# Un_51_V1_0.net
KiCad netlist of a schematic drawn in EAGLE
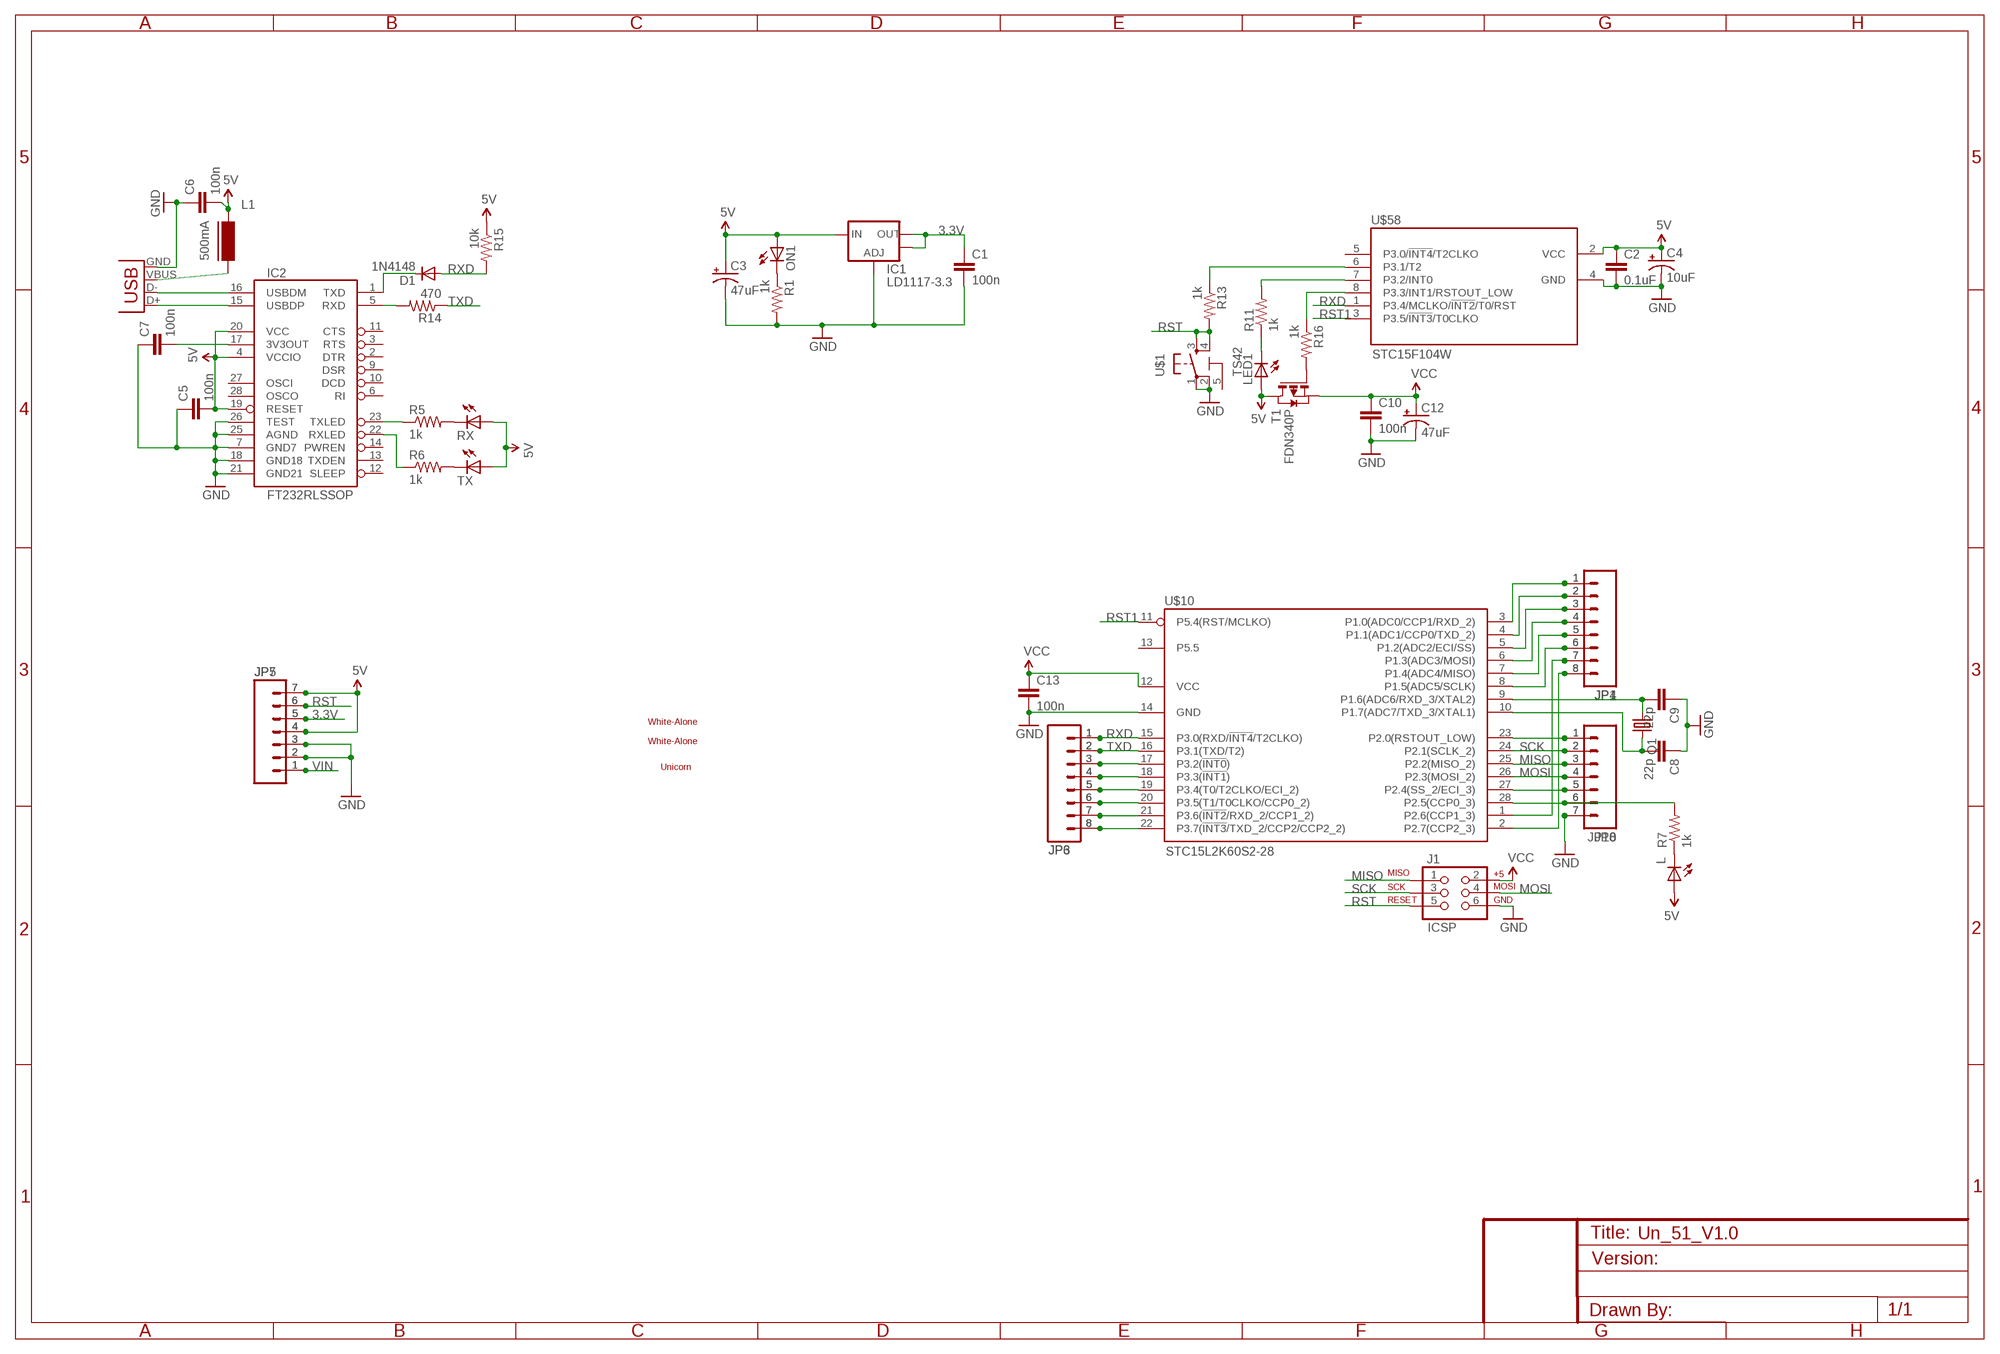
[diagram p0: schematic, sheet 1]

(export (version "E")
  (design (tool "Eeschema 10.0.6"))
  (components
    (comp (ref "C1")
      (value "100n")
      (footprint "eagle-import:0603-CAP")
      (libsource (lib "eagle-import") (part "2SparkFun_CAP0603-CAP"))
    )
    (comp (ref "C2")
      (value "0.1uF")
      (footprint "eagle-import:0603-CAP")
      (libsource (lib "eagle-import") (part "2SparkFun_CAP0603-CAP"))
    )
    (comp (ref "C3")
      (value "47uF")
      (footprint "eagle-import:PANASONIC_D")
      (libsource (lib "eagle-import") (part "CAP_POLD"))
    )
    (comp (ref "C4")
      (value "10uF")
      (footprint "eagle-import:EIA3216")
      (libsource (lib "eagle-import") (part "CAP_POL1206"))
    )
    (comp (ref "C5")
      (value "100n")
      (footprint "eagle-import:0603-CAP")
      (libsource (lib "eagle-import") (part "2SparkFun_CAP0603-CAP"))
    )
    (comp (ref "C6")
      (value "100n")
      (footprint "eagle-import:0603-CAP")
      (libsource (lib "eagle-import") (part "2SparkFun_CAP0603-CAP"))
    )
    (comp (ref "C7")
      (value "100n")
      (footprint "eagle-import:0603-CAP")
      (libsource (lib "eagle-import") (part "2SparkFun_CAP0603-CAP"))
    )
    (comp (ref "C8")
      (value "22p")
      (footprint "eagle-import:0603-CAP")
      (libsource (lib "eagle-import") (part "2SparkFun_CAP0603-CAP"))
    )
    (comp (ref "C9")
      (value "22p")
      (footprint "eagle-import:0603-CAP")
      (libsource (lib "eagle-import") (part "2SparkFun_CAP0603-CAP"))
    )
    (comp (ref "C10")
      (value "100n")
      (footprint "eagle-import:0603-CAP")
      (libsource (lib "eagle-import") (part "2SparkFun_CAP0603-CAP"))
    )
    (comp (ref "C12")
      (value "47uF")
      (footprint "eagle-import:PANASONIC_D")
      (libsource (lib "eagle-import") (part "CAP_POLD"))
    )
    (comp (ref "C13")
      (value "100n")
      (footprint "eagle-import:0603-CAP")
      (libsource (lib "eagle-import") (part "CAP0603-CAP"))
    )
    (comp (ref "D1")
      (value "1N4148")
      (footprint "eagle-import:SOD-323")
      (libsource (lib "eagle-import") (part "DIODESOD"))
    )
    (comp (ref "IC1")
      (value "LD1117-3.3")
      (footprint "eagle-import:SOT223")
      (libsource (lib "eagle-import") (part "V_REG_LM1117SOT223"))
    )
    (comp (ref "IC2")
      (value "FT232RLSSOP")
      (footprint "eagle-import:SSOP28DB")
      (libsource (lib "eagle-import") (part "FT232RLSSOP"))
    )
    (comp (ref "J1")
      (value "ICSP")
      (footprint "eagle-import:2X3")
      (libsource (lib "eagle-import") (part "AVR_SPI_PRG_6PTH"))
    )
    (comp (ref "JP1")
      (value "M081X08")
      (footprint "eagle-import:1X08")
      (libsource (lib "eagle-import") (part "M081X08"))
    )
    (comp (ref "JP3")
      (value "M08")
      (footprint "eagle-import:1X08")
      (libsource (lib "eagle-import") (part "M08"))
    )
    (comp (ref "JP4")
      (value "M081X08")
      (footprint "eagle-import:1X08")
      (libsource (lib "eagle-import") (part "M081X08"))
    )
    (comp (ref "JP5")
      (value "M07")
      (footprint "eagle-import:1X07")
      (libsource (lib "eagle-import") (part "M07"))
    )
    (comp (ref "JP6")
      (value "M08")
      (footprint "eagle-import:1X08")
      (libsource (lib "eagle-import") (part "M08"))
    )
    (comp (ref "JP7")
      (value "M07")
      (footprint "eagle-import:1X07")
      (libsource (lib "eagle-import") (part "M07"))
    )
    (comp (ref "JP8")
      (value "M07")
      (footprint "eagle-import:1X07")
      (libsource (lib "eagle-import") (part "M07"))
    )
    (comp (ref "JP10")
      (value "M07")
      (footprint "eagle-import:1X07")
      (libsource (lib "eagle-import") (part "M07"))
    )
    (comp (ref "L")
      (value "LED0805")
      (footprint "eagle-import:LED-0805")
      (libsource (lib "eagle-import") (part "LED0805"))
    )
    (comp (ref "L1")
      (value "500mA")
      (footprint "eagle-import:FB805")
      (libsource (lib "eagle-import") (part "FERRITE-0805"))
    )
    (comp (ref "LED1")
      (value "LED0805")
      (footprint "eagle-import:LED-0805")
      (libsource (lib "eagle-import") (part "2SparkFun_LED0805"))
    )
    (comp (ref "ON1")
      (value "LED0805")
      (footprint "eagle-import:LED-0805")
      (libsource (lib "eagle-import") (part "LED0805"))
    )
    (comp (ref "Q1")
      (value "CRYSTALHC49US")
      (footprint "eagle-import:HC49US")
      (libsource (lib "eagle-import") (part "CRYSTALHC49US"))
    )
    (comp (ref "R1")
      (value "1k")
      (footprint "eagle-import:0603-RES")
      (libsource (lib "eagle-import") (part "RESISTOR0603-RES"))
    )
    (comp (ref "R5")
      (value "1k")
      (footprint "eagle-import:0603-RES")
      (libsource (lib "eagle-import") (part "RESISTOR0603-RES"))
    )
    (comp (ref "R6")
      (value "1k")
      (footprint "eagle-import:0603-RES")
      (libsource (lib "eagle-import") (part "RESISTOR0603-RES"))
    )
    (comp (ref "R7")
      (value "1k")
      (footprint "eagle-import:0603-RES")
      (libsource (lib "eagle-import") (part "RESISTOR0603-RES"))
    )
    (comp (ref "R11")
      (value "1k")
      (footprint "eagle-import:0603-RES")
      (libsource (lib "eagle-import") (part "RESISTOR0603-RES"))
    )
    (comp (ref "R13")
      (value "1k")
      (footprint "eagle-import:0603-RES")
      (libsource (lib "eagle-import") (part "RESISTOR0603-RES"))
    )
    (comp (ref "R14")
      (value "470")
      (footprint "eagle-import:0603-RES")
      (libsource (lib "eagle-import") (part "RESISTOR0603-RES"))
    )
    (comp (ref "R15")
      (value "10k")
      (footprint "eagle-import:0603-RES")
      (libsource (lib "eagle-import") (part "RESISTOR0603-RES"))
    )
    (comp (ref "R16")
      (value "1k")
      (footprint "eagle-import:0603-RES")
      (libsource (lib "eagle-import") (part "RESISTOR0603-RES"))
    )
    (comp (ref "RX")
      (value "LED0805")
      (footprint "eagle-import:LED-0805")
      (libsource (lib "eagle-import") (part "LED0805"))
    )
    (comp (ref "T1")
      (value "FDN340P")
      (footprint "eagle-import:SOT-23")
      (libsource (lib "eagle-import") (part "PMOSSOT23"))
    )
    (comp (ref "TX")
      (value "LED0805")
      (footprint "eagle-import:LED-0805")
      (libsource (lib "eagle-import") (part "LED0805"))
    )
    (comp (ref "U$1")
      (value "TS42")
      (footprint "eagle-import:TS42")
      (libsource (lib "eagle-import") (part "TS42"))
    )
    (comp (ref "U$3")
      (value "UNICORN")
      (footprint "eagle-import:UNICORN_1")
      (libsource (lib "eagle-import") (part "UNICORN"))
    )
    (comp (ref "U$7")
      (value "WHITE-ALONE_0")
      (footprint "eagle-import:WHITE-ALONE_0")
      (libsource (lib "eagle-import") (part "WHITE-ALONE_0"))
    )
    (comp (ref "U$10")
      (value "STC15L2K60S2-28")
      (footprint "eagle-import:SO-28W")
      (libsource (lib "eagle-import") (part "STC15L2K60S2-28"))
    )
    (comp (ref "U$11")
      (value "WHITE-ALONE_0")
      (footprint "eagle-import:WHITE-ALONE_0")
      (libsource (lib "eagle-import") (part "WHITE-ALONE_0"))
    )
    (comp (ref "U$58")
      (value "STC15F104W")
      (footprint "eagle-import:SO08")
      (libsource (lib "eagle-import") (part "STC15F104W"))
    )
    (comp (ref "X1")
      (value "USBSMD")
      (footprint "eagle-import:USB-MINIB")
      (libsource (lib "eagle-import") (part "USBSMD"))
    )
  )
  (nets
    (net (code "1") (name "/3.3V") (class "Default")
      (node (ref "C1") (pin "1") (pinfunction "1_1") (pintype "passive"))
      (node (ref "IC1") (pin "2") (pinfunction "OUT_2") (pintype "output"))
      (node (ref "IC1") (pin "4") (pinfunction "OUT_4") (pintype "output"))
      (node (ref "JP5") (pin "5") (pinfunction "5_5") (pintype "passive"))
      (node (ref "JP7") (pin "5") (pinfunction "5_5") (pintype "passive"))
    )
    (net (code "2") (name "/MISO") (class "Default")
      (node (ref "J1") (pin "1") (pinfunction "1_1") (pintype "passive"))
      (node (ref "JP10") (pin "3") (pinfunction "3_3") (pintype "passive"))
      (node (ref "JP8") (pin "3") (pinfunction "3_3") (pintype "passive"))
      (node (ref "U$10") (pin "25") (pinfunction "P2.2(MISO_2)_25") (pintype "bidirectional"))
    )
    (net (code "3") (name "/MOSI") (class "Default")
      (node (ref "J1") (pin "4") (pinfunction "4_4") (pintype "passive"))
      (node (ref "JP10") (pin "4") (pinfunction "4_4") (pintype "passive"))
      (node (ref "JP8") (pin "4") (pinfunction "4_4") (pintype "passive"))
      (node (ref "U$10") (pin "26") (pinfunction "P2.3(MOSI_2)_26") (pintype "bidirectional"))
    )
    (net (code "4") (name "/RST") (class "Default")
      (node (ref "J1") (pin "5") (pinfunction "5_5") (pintype "passive"))
      (node (ref "JP5") (pin "6") (pinfunction "6_6") (pintype "passive"))
      (node (ref "JP7") (pin "6") (pinfunction "6_6") (pintype "passive"))
      (node (ref "R13") (pin "2") (pinfunction "2_2") (pintype "passive"))
      (node (ref "U$1") (pin "3") (pinfunction "3_3") (pintype "passive"))
      (node (ref "U$1") (pin "4") (pinfunction "4_4") (pintype "passive"))
    )
    (net (code "5") (name "/RST1") (class "Default")
      (node (ref "U$10") (pin "11") (pinfunction "P5.4(RST/MCLKO)_11") (pintype "bidirectional"))
      (node (ref "U$58") (pin "3") (pinfunction "P3.5/~{INT3}/T0CLKO_3") (pintype "bidirectional"))
    )
    (net (code "6") (name "/RXD") (class "Default")
      (node (ref "D1") (pin "2") (pinfunction "A_2") (pintype "passive"))
      (node (ref "JP3") (pin "1") (pinfunction "1_1") (pintype "passive"))
      (node (ref "JP6") (pin "1") (pinfunction "1_1") (pintype "passive"))
      (node (ref "R15") (pin "2") (pinfunction "2_2") (pintype "passive"))
      (node (ref "U$10") (pin "15") (pinfunction "P3.0(RXD/~{INT4}/T2CLKO)_15") (pintype "bidirectional"))
      (node (ref "U$58") (pin "1") (pinfunction "P3.4/MCLKO/~{INT2}/T0/RST_1") (pintype "bidirectional"))
    )
    (net (code "7") (name "/SCK") (class "Default")
      (node (ref "J1") (pin "3") (pinfunction "3_3") (pintype "passive"))
      (node (ref "JP10") (pin "2") (pinfunction "2_2") (pintype "passive"))
      (node (ref "JP8") (pin "2") (pinfunction "2_2") (pintype "passive"))
      (node (ref "U$10") (pin "24") (pinfunction "P2.1(SCLK_2)_24") (pintype "bidirectional"))
    )
    (net (code "8") (name "/TXD") (class "Default")
      (node (ref "JP3") (pin "2") (pinfunction "2_2") (pintype "passive"))
      (node (ref "JP6") (pin "2") (pinfunction "2_2") (pintype "passive"))
      (node (ref "R14") (pin "1") (pinfunction "1_1") (pintype "passive"))
      (node (ref "U$10") (pin "16") (pinfunction "P3.1(TXD/T2)_16") (pintype "bidirectional"))
    )
    (net (code "9") (name "/VIN") (class "Default")
      (node (ref "JP5") (pin "1") (pinfunction "1_1") (pintype "passive"))
      (node (ref "JP7") (pin "1") (pinfunction "1_1") (pintype "passive"))
    )
    (net (code "10") (name "5V") (class "Default")
      (node (ref "C2") (pin "1") (pinfunction "1_1") (pintype "passive"))
      (node (ref "C3") (pin "+") (pinfunction "+_+") (pintype "passive"))
      (node (ref "C4") (pin "A") (pinfunction "+_A") (pintype "passive"))
      (node (ref "C5") (pin "2") (pinfunction "2_2") (pintype "passive"))
      (node (ref "C6") (pin "2") (pinfunction "2_2") (pintype "passive"))
      (node (ref "IC1") (pin "3") (pinfunction "IN_3") (pintype "input"))
      (node (ref "IC2") (pin "19") (pinfunction "RESET_19") (pintype "input"))
      (node (ref "IC2") (pin "20") (pinfunction "VCC_20") (pintype "power_in"))
      (node (ref "IC2") (pin "4") (pinfunction "VCCIO_4") (pintype "power_in"))
      (node (ref "JP5") (pin "4") (pinfunction "4_4") (pintype "passive"))
      (node (ref "JP5") (pin "7") (pinfunction "7_7") (pintype "passive"))
      (node (ref "JP7") (pin "4") (pinfunction "4_4") (pintype "passive"))
      (node (ref "JP7") (pin "7") (pinfunction "7_7") (pintype "passive"))
      (node (ref "L") (pin "1") (pinfunction "A_1") (pintype "passive"))
      (node (ref "L1") (pin "1") (pinfunction "1_1") (pintype "passive"))
      (node (ref "LED1") (pin "1") (pinfunction "A_1") (pintype "passive"))
      (node (ref "ON1") (pin "1") (pinfunction "A_1") (pintype "passive"))
      (node (ref "R15") (pin "1") (pinfunction "1_1") (pintype "passive"))
      (node (ref "RX") (pin "1") (pinfunction "A_1") (pintype "passive"))
      (node (ref "T1") (pin "1") (pinfunction "D_1") (pintype "passive"))
      (node (ref "TX") (pin "1") (pinfunction "A_1") (pintype "passive"))
      (node (ref "U$58") (pin "2") (pinfunction "VCC_2") (pintype "bidirectional"))
    )
    (net (code "11") (name "GND") (class "Default")
      (node (ref "C1") (pin "2") (pinfunction "2_2") (pintype "passive"))
      (node (ref "C10") (pin "2") (pinfunction "2_2") (pintype "passive"))
      (node (ref "C12") (pin "-") (pinfunction "-_-") (pintype "passive"))
      (node (ref "C13") (pin "2") (pinfunction "2_2") (pintype "passive"))
      (node (ref "C2") (pin "2") (pinfunction "2_2") (pintype "passive"))
      (node (ref "C3") (pin "-") (pinfunction "-_-") (pintype "passive"))
      (node (ref "C4") (pin "C") (pinfunction "-_C") (pintype "passive"))
      (node (ref "C5") (pin "1") (pinfunction "1_1") (pintype "passive"))
      (node (ref "C6") (pin "1") (pinfunction "1_1") (pintype "passive"))
      (node (ref "C7") (pin "1") (pinfunction "1_1") (pintype "passive"))
      (node (ref "C8") (pin "1") (pinfunction "1_1") (pintype "passive"))
      (node (ref "C9") (pin "1") (pinfunction "1_1") (pintype "passive"))
      (node (ref "IC1") (pin "1") (pinfunction "ADJ_1") (pintype "input"))
      (node (ref "IC2") (pin "18") (pinfunction "GND18_18") (pintype "power_in"))
      (node (ref "IC2") (pin "21") (pinfunction "GND21_21") (pintype "power_in"))
      (node (ref "IC2") (pin "25") (pinfunction "AGND_25") (pintype "power_in"))
      (node (ref "IC2") (pin "26") (pinfunction "TEST_26") (pintype "input"))
      (node (ref "IC2") (pin "7") (pinfunction "GND7_7") (pintype "power_in"))
      (node (ref "J1") (pin "6") (pinfunction "6_6") (pintype "passive"))
      (node (ref "JP10") (pin "7") (pinfunction "7_7") (pintype "passive"))
      (node (ref "JP5") (pin "2") (pinfunction "2_2") (pintype "passive"))
      (node (ref "JP5") (pin "3") (pinfunction "3_3") (pintype "passive"))
      (node (ref "JP7") (pin "2") (pinfunction "2_2") (pintype "passive"))
      (node (ref "JP7") (pin "3") (pinfunction "3_3") (pintype "passive"))
      (node (ref "JP8") (pin "7") (pinfunction "7_7") (pintype "passive"))
      (node (ref "R1") (pin "2") (pinfunction "2_2") (pintype "passive"))
      (node (ref "U$1") (pin "1") (pinfunction "1_1") (pintype "passive"))
      (node (ref "U$1") (pin "2") (pinfunction "2_2") (pintype "passive"))
      (node (ref "U$10") (pin "14") (pinfunction "GND_14") (pintype "bidirectional"))
      (node (ref "U$58") (pin "4") (pinfunction "GND_4") (pintype "bidirectional"))
      (node (ref "X1") (pin "GND") (pinfunction "GND_GND") (pintype "bidirectional"))
    )
    (net (code "12") (name "Net-(D1-C)") (class "Default")
      (node (ref "D1") (pin "1") (pinfunction "C_1") (pintype "passive"))
      (node (ref "IC2") (pin "1") (pinfunction "TXD_1") (pintype "output"))
    )
    (net (code "13") (name "Net-(IC2-3V3OUT)") (class "Default")
      (node (ref "C7") (pin "2") (pinfunction "2_2") (pintype "passive"))
      (node (ref "IC2") (pin "17") (pinfunction "3V3OUT_17") (pintype "output"))
    )
    (net (code "14") (name "Net-(IC2-RXD)") (class "Default")
      (node (ref "IC2") (pin "5") (pinfunction "RXD_5") (pintype "input"))
      (node (ref "R14") (pin "2") (pinfunction "2_2") (pintype "passive"))
    )
    (net (code "15") (name "Net-(IC2-RXLED)") (class "Default")
      (node (ref "IC2") (pin "22") (pinfunction "RXLED_22") (pintype "input"))
      (node (ref "R6") (pin "1") (pinfunction "1_1") (pintype "passive"))
    )
    (net (code "16") (name "Net-(IC2-TXLED)") (class "Default")
      (node (ref "IC2") (pin "23") (pinfunction "TXLED_23") (pintype "input"))
      (node (ref "R5") (pin "1") (pinfunction "1_1") (pintype "passive"))
    )
    (net (code "17") (name "Net-(IC2-USBDM)") (class "Default")
      (node (ref "IC2") (pin "16") (pinfunction "USBDM_16") (pintype "bidirectional"))
      (node (ref "X1") (pin "D-") (pinfunction "D-_D-") (pintype "bidirectional"))
    )
    (net (code "18") (name "Net-(IC2-USBDP)") (class "Default")
      (node (ref "IC2") (pin "15") (pinfunction "USBDP_15") (pintype "bidirectional"))
      (node (ref "X1") (pin "D+") (pinfunction "D+_D+") (pintype "bidirectional"))
    )
    (net (code "19") (name "Net-(L-C)") (class "Default")
      (node (ref "L") (pin "2") (pinfunction "C_2") (pintype "passive"))
      (node (ref "R7") (pin "1") (pinfunction "1_1") (pintype "passive"))
    )
    (net (code "20") (name "Net-(L1-Pad2)") (class "Default")
      (node (ref "L1") (pin "2") (pinfunction "2_2") (pintype "passive"))
      (node (ref "X1") (pin "VBUS") (pinfunction "VBUS_VBUS") (pintype "bidirectional"))
    )
    (net (code "21") (name "Net-(LED1-C)") (class "Default")
      (node (ref "LED1") (pin "2") (pinfunction "C_2") (pintype "passive"))
      (node (ref "R11") (pin "1") (pinfunction "1_1") (pintype "passive"))
    )
    (net (code "22") (name "Net-(ON1-C)") (class "Default")
      (node (ref "ON1") (pin "2") (pinfunction "C_2") (pintype "passive"))
      (node (ref "R1") (pin "1") (pinfunction "1_1") (pintype "passive"))
    )
    (net (code "23") (name "Net-(RX-C)") (class "Default")
      (node (ref "R5") (pin "2") (pinfunction "2_2") (pintype "passive"))
      (node (ref "RX") (pin "2") (pinfunction "C_2") (pintype "passive"))
    )
    (net (code "24") (name "Net-(T1-G)") (class "Default")
      (node (ref "R16") (pin "2") (pinfunction "2_2") (pintype "passive"))
      (node (ref "T1") (pin "3") (pinfunction "G_3") (pintype "passive"))
    )
    (net (code "25") (name "Net-(TX-C)") (class "Default")
      (node (ref "R6") (pin "2") (pinfunction "2_2") (pintype "passive"))
      (node (ref "TX") (pin "2") (pinfunction "C_2") (pintype "passive"))
    )
    (net (code "26") (name "Net-(U$10-P1.0(ADC0{slash}CCP1{slash}RXD_2))") (class "Default")
      (node (ref "JP1") (pin "1") (pinfunction "1_1") (pintype "passive"))
      (node (ref "JP4") (pin "1") (pinfunction "1_1") (pintype "passive"))
      (node (ref "U$10") (pin "3") (pinfunction "P1.0(ADC0/CCP1/RXD_2)_3") (pintype "bidirectional"))
    )
    (net (code "27") (name "Net-(U$10-P1.1(ADC1{slash}CCP0{slash}TXD_2))") (class "Default")
      (node (ref "JP1") (pin "2") (pinfunction "2_2") (pintype "passive"))
      (node (ref "JP4") (pin "2") (pinfunction "2_2") (pintype "passive"))
      (node (ref "U$10") (pin "4") (pinfunction "P1.1(ADC1/CCP0/TXD_2)_4") (pintype "bidirectional"))
    )
    (net (code "28") (name "Net-(U$10-P1.2(ADC2{slash}ECI{slash}SS))") (class "Default")
      (node (ref "JP1") (pin "3") (pinfunction "3_3") (pintype "passive"))
      (node (ref "JP4") (pin "3") (pinfunction "3_3") (pintype "passive"))
      (node (ref "U$10") (pin "5") (pinfunction "P1.2(ADC2/ECI/SS)_5") (pintype "bidirectional"))
    )
    (net (code "29") (name "Net-(U$10-P1.3(ADC3{slash}MOSI))") (class "Default")
      (node (ref "JP1") (pin "4") (pinfunction "4_4") (pintype "passive"))
      (node (ref "JP4") (pin "4") (pinfunction "4_4") (pintype "passive"))
      (node (ref "U$10") (pin "6") (pinfunction "P1.3(ADC3/MOSI)_6") (pintype "bidirectional"))
    )
    (net (code "30") (name "Net-(U$10-P1.4(ADC4{slash}MISO))") (class "Default")
      (node (ref "JP1") (pin "5") (pinfunction "5_5") (pintype "passive"))
      (node (ref "JP4") (pin "5") (pinfunction "5_5") (pintype "passive"))
      (node (ref "U$10") (pin "7") (pinfunction "P1.4(ADC4/MISO)_7") (pintype "bidirectional"))
    )
    (net (code "31") (name "Net-(U$10-P1.5(ADC5{slash}SCLK))") (class "Default")
      (node (ref "JP1") (pin "6") (pinfunction "6_6") (pintype "passive"))
      (node (ref "JP4") (pin "6") (pinfunction "6_6") (pintype "passive"))
      (node (ref "U$10") (pin "8") (pinfunction "P1.5(ADC5/SCLK)_8") (pintype "bidirectional"))
    )
    (net (code "32") (name "Net-(U$10-P1.6(ADC6{slash}RXD_3{slash}XTAL2))") (class "Default")
      (node (ref "C9") (pin "2") (pinfunction "2_2") (pintype "passive"))
      (node (ref "Q1") (pin "1") (pinfunction "1_1") (pintype "passive"))
      (node (ref "U$10") (pin "9") (pinfunction "P1.6(ADC6/RXD_3/XTAL2)_9") (pintype "bidirectional"))
    )
    (net (code "33") (name "Net-(U$10-P1.7(ADC7{slash}TXD_3{slash}XTAL1))") (class "Default")
      (node (ref "C8") (pin "2") (pinfunction "2_2") (pintype "passive"))
      (node (ref "Q1") (pin "2") (pinfunction "2_2") (pintype "passive"))
      (node (ref "U$10") (pin "10") (pinfunction "P1.7(ADC7/TXD_3/XTAL1)_10") (pintype "bidirectional"))
    )
    (net (code "34") (name "Net-(U$10-P2.0(RSTOUT_LOW))") (class "Default")
      (node (ref "JP10") (pin "1") (pinfunction "1_1") (pintype "passive"))
      (node (ref "JP8") (pin "1") (pinfunction "1_1") (pintype "passive"))
      (node (ref "U$10") (pin "23") (pinfunction "P2.0(RSTOUT_LOW)_23") (pintype "bidirectional"))
    )
    (net (code "35") (name "Net-(U$10-P2.4(SS_2{slash}ECI_3))") (class "Default")
      (node (ref "JP10") (pin "5") (pinfunction "5_5") (pintype "passive"))
      (node (ref "JP8") (pin "5") (pinfunction "5_5") (pintype "passive"))
      (node (ref "U$10") (pin "27") (pinfunction "P2.4(SS_2/ECI_3)_27") (pintype "bidirectional"))
    )
    (net (code "36") (name "Net-(U$10-P2.5(CCP0_3))") (class "Default")
      (node (ref "JP10") (pin "6") (pinfunction "6_6") (pintype "passive"))
      (node (ref "JP8") (pin "6") (pinfunction "6_6") (pintype "passive"))
      (node (ref "R7") (pin "2") (pinfunction "2_2") (pintype "passive"))
      (node (ref "U$10") (pin "28") (pinfunction "P2.5(CCP0_3)_28") (pintype "bidirectional"))
    )
    (net (code "37") (name "Net-(U$10-P2.6(CCP1_3))") (class "Default")
      (node (ref "JP1") (pin "7") (pinfunction "7_7") (pintype "passive"))
      (node (ref "JP4") (pin "7") (pinfunction "7_7") (pintype "passive"))
      (node (ref "U$10") (pin "1") (pinfunction "P2.6(CCP1_3)_1") (pintype "bidirectional"))
    )
    (net (code "38") (name "Net-(U$10-P2.7(CCP2_3))") (class "Default")
      (node (ref "JP1") (pin "8") (pinfunction "8_8") (pintype "passive"))
      (node (ref "JP4") (pin "8") (pinfunction "8_8") (pintype "passive"))
      (node (ref "U$10") (pin "2") (pinfunction "P2.7(CCP2_3)_2") (pintype "bidirectional"))
    )
    (net (code "39") (name "Net-(U$10-P3.2(~{INT0}))") (class "Default")
      (node (ref "JP3") (pin "3") (pinfunction "3_3") (pintype "passive"))
      (node (ref "JP6") (pin "3") (pinfunction "3_3") (pintype "passive"))
      (node (ref "U$10") (pin "17") (pinfunction "P3.2(~{INT0})_17") (pintype "bidirectional"))
    )
    (net (code "40") (name "Net-(U$10-P3.3(~{INT1}))") (class "Default")
      (node (ref "JP3") (pin "4") (pinfunction "4_4") (pintype "passive"))
      (node (ref "JP6") (pin "4") (pinfunction "4_4") (pintype "passive"))
      (node (ref "U$10") (pin "18") (pinfunction "P3.3(~{INT1})_18") (pintype "bidirectional"))
    )
    (net (code "41") (name "Net-(U$10-P3.4(T0{slash}T2CLKO{slash}ECI_2))") (class "Default")
      (node (ref "JP3") (pin "5") (pinfunction "5_5") (pintype "passive"))
      (node (ref "JP6") (pin "5") (pinfunction "5_5") (pintype "passive"))
      (node (ref "U$10") (pin "19") (pinfunction "P3.4(T0/T2CLKO/ECI_2)_19") (pintype "bidirectional"))
    )
    (net (code "42") (name "Net-(U$10-P3.5(T1{slash}T0CLKO{slash}CCP0_2))") (class "Default")
      (node (ref "JP3") (pin "6") (pinfunction "6_6") (pintype "passive"))
      (node (ref "JP6") (pin "6") (pinfunction "6_6") (pintype "passive"))
      (node (ref "U$10") (pin "20") (pinfunction "P3.5(T1/T0CLKO/CCP0_2)_20") (pintype "bidirectional"))
    )
    (net (code "43") (name "Net-(U$10-P3.6(~{INT2}{slash}RXD_2{slash}CCP1_2))") (class "Default")
      (node (ref "JP3") (pin "7") (pinfunction "7_7") (pintype "passive"))
      (node (ref "JP6") (pin "7") (pinfunction "7_7") (pintype "passive"))
      (node (ref "U$10") (pin "21") (pinfunction "P3.6(~{INT2}/RXD_2/CCP1_2)_21") (pintype "bidirectional"))
    )
    (net (code "44") (name "Net-(U$10-P3.7(~{INT3}{slash}TXD_2{slash}CCP2{slash}CCP2_2))") (class "Default")
      (node (ref "JP3") (pin "8") (pinfunction "8_8") (pintype "passive"))
      (node (ref "JP6") (pin "8") (pinfunction "8_8") (pintype "passive"))
      (node (ref "U$10") (pin "22") (pinfunction "P3.7(~{INT3}/TXD_2/CCP2/CCP2_2)_22") (pintype "bidirectional"))
    )
    (net (code "45") (name "Net-(U$58-P3.1{slash}T2)") (class "Default")
      (node (ref "R13") (pin "1") (pinfunction "1_1") (pintype "passive"))
      (node (ref "U$58") (pin "6") (pinfunction "P3.1/T2_6") (pintype "bidirectional"))
    )
    (net (code "46") (name "Net-(U$58-P3.2{slash}INT0)") (class "Default")
      (node (ref "R11") (pin "2") (pinfunction "2_2") (pintype "passive"))
      (node (ref "U$58") (pin "7") (pinfunction "P3.2/INT0_7") (pintype "bidirectional"))
    )
    (net (code "47") (name "Net-(U$58-P3.3{slash}INT1{slash}RSTOUT_LOW)") (class "Default")
      (node (ref "R16") (pin "1") (pinfunction "1_1") (pintype "passive"))
      (node (ref "U$58") (pin "8") (pinfunction "P3.3/INT1/RSTOUT_LOW_8") (pintype "bidirectional"))
    )
    (net (code "48") (name "VCC") (class "Default")
      (node (ref "C10") (pin "1") (pinfunction "1_1") (pintype "passive"))
      (node (ref "C12") (pin "+") (pinfunction "+_+") (pintype "passive"))
      (node (ref "C13") (pin "1") (pinfunction "1_1") (pintype "passive"))
      (node (ref "J1") (pin "2") (pinfunction "2_2") (pintype "passive"))
      (node (ref "T1") (pin "2") (pinfunction "S_2") (pintype "passive"))
      (node (ref "U$10") (pin "12") (pinfunction "VCC_12") (pintype "bidirectional"))
    )
    (net (code "49") (name "unconnected-(IC2-CTS-Pad11)") (class "Default")
      (node (ref "IC2") (pin "11") (pinfunction "CTS_11") (pintype "input"))
    )
    (net (code "50") (name "unconnected-(IC2-DCD-Pad10)") (class "Default")
      (node (ref "IC2") (pin "10") (pinfunction "DCD_10") (pintype "input"))
    )
    (net (code "51") (name "unconnected-(IC2-DSR-Pad9)") (class "Default")
      (node (ref "IC2") (pin "9") (pinfunction "DSR_9") (pintype "input"))
    )
    (net (code "52") (name "unconnected-(IC2-DTR-Pad2)") (class "Default")
      (node (ref "IC2") (pin "2") (pinfunction "DTR_2") (pintype "output"))
    )
    (net (code "53") (name "unconnected-(IC2-OSCI-Pad27)") (class "Default")
      (node (ref "IC2") (pin "27") (pinfunction "OSCI_27") (pintype "input"))
    )
    (net (code "54") (name "unconnected-(IC2-OSCO-Pad28)") (class "Default")
      (node (ref "IC2") (pin "28") (pinfunction "OSCO_28") (pintype "output"))
    )
    (net (code "55") (name "unconnected-(IC2-PWREN-Pad14)") (class "Default")
      (node (ref "IC2") (pin "14") (pinfunction "PWREN_14") (pintype "input"))
    )
    (net (code "56") (name "unconnected-(IC2-RI-Pad6)") (class "Default")
      (node (ref "IC2") (pin "6") (pinfunction "RI_6") (pintype "input"))
    )
    (net (code "57") (name "unconnected-(IC2-RTS-Pad3)") (class "Default")
      (node (ref "IC2") (pin "3") (pinfunction "RTS_3") (pintype "output"))
    )
    (net (code "58") (name "unconnected-(IC2-SLEEP-Pad12)") (class "Default")
      (node (ref "IC2") (pin "12") (pinfunction "SLEEP_12") (pintype "input"))
    )
    (net (code "59") (name "unconnected-(IC2-TXDEN-Pad13)") (class "Default")
      (node (ref "IC2") (pin "13") (pinfunction "TXDEN_13") (pintype "input"))
    )
    (net (code "60") (name "unconnected-(U$1-Pad5)") (class "Default")
      (node (ref "U$1") (pin "5") (pinfunction "5_5") (pintype "passive"))
    )
    (net (code "61") (name "unconnected-(U$10-P5.5-Pad13)") (class "Default")
      (node (ref "U$10") (pin "13") (pinfunction "P5.5_13") (pintype "bidirectional"))
    )
    (net (code "62") (name "unconnected-(U$58-P3.0{slash}~{INT4}{slash}T2CLKO-Pad5)") (class "Default")
      (node (ref "U$58") (pin "5") (pinfunction "P3.0/~{INT4}/T2CLKO_5") (pintype "bidirectional"))
    )
  )
)
